# Twintig-FFC-Metacarpal-RA.net
KiCad netlist of a schematic drawn in Altium Designer
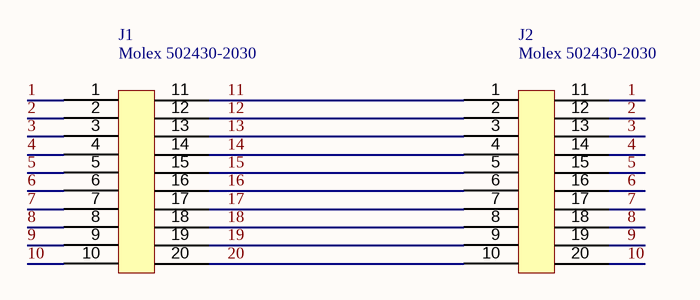
[diagram p0: Twintig-FFC-Metacarpal-RA.SchDoc]

(export (version "E")
  (design (tool "Eeschema 10.0.6"))
  (components
    (comp (ref "J1")
      (value "Molex 502430-2030")
      (footprint "Molex 502430-2030")
      (libsource (lib "x-io") (part "Molex 502430-2030"))
    )
    (comp (ref "J2")
      (value "Molex 502430-2030")
      (footprint "Molex 502430-2030")
      (libsource (lib "x-io") (part "Molex 502430-2030"))
    )
  )
  (nets
    (net (code "1") (name "/1") (class "Default")
      (node (ref "J1") (pin "1") (pinfunction "1_1") (pintype "passive"))
      (node (ref "J2") (pin "11") (pinfunction "11_11") (pintype "passive"))
    )
    (net (code "2") (name "/2") (class "Default")
      (node (ref "J1") (pin "2") (pinfunction "2_2") (pintype "passive"))
      (node (ref "J2") (pin "12") (pinfunction "12_12") (pintype "passive"))
    )
    (net (code "3") (name "/3") (class "Default")
      (node (ref "J1") (pin "3") (pinfunction "3_3") (pintype "passive"))
      (node (ref "J2") (pin "13") (pinfunction "13_13") (pintype "passive"))
    )
    (net (code "4") (name "/4") (class "Default")
      (node (ref "J1") (pin "4") (pinfunction "4_4") (pintype "passive"))
      (node (ref "J2") (pin "14") (pinfunction "14_14") (pintype "passive"))
    )
    (net (code "5") (name "/5") (class "Default")
      (node (ref "J1") (pin "5") (pinfunction "5_5") (pintype "passive"))
      (node (ref "J2") (pin "15") (pinfunction "15_15") (pintype "passive"))
    )
    (net (code "6") (name "/6") (class "Default")
      (node (ref "J1") (pin "6") (pinfunction "6_6") (pintype "passive"))
      (node (ref "J2") (pin "16") (pinfunction "16_16") (pintype "passive"))
    )
    (net (code "7") (name "/7") (class "Default")
      (node (ref "J1") (pin "7") (pinfunction "7_7") (pintype "passive"))
      (node (ref "J2") (pin "17") (pinfunction "17_17") (pintype "passive"))
    )
    (net (code "8") (name "/8") (class "Default")
      (node (ref "J1") (pin "8") (pinfunction "8_8") (pintype "passive"))
      (node (ref "J2") (pin "18") (pinfunction "18_18") (pintype "passive"))
    )
    (net (code "9") (name "/9") (class "Default")
      (node (ref "J1") (pin "9") (pinfunction "9_9") (pintype "passive"))
      (node (ref "J2") (pin "19") (pinfunction "19_19") (pintype "passive"))
    )
    (net (code "10") (name "/10") (class "Default")
      (node (ref "J1") (pin "10") (pinfunction "10_10") (pintype "passive"))
      (node (ref "J2") (pin "20") (pinfunction "20_20") (pintype "passive"))
    )
    (net (code "11") (name "/11") (class "Default")
      (node (ref "J1") (pin "11") (pinfunction "11_11") (pintype "passive"))
      (node (ref "J2") (pin "1") (pinfunction "1_1") (pintype "passive"))
    )
    (net (code "12") (name "/12") (class "Default")
      (node (ref "J1") (pin "12") (pinfunction "12_12") (pintype "passive"))
      (node (ref "J2") (pin "2") (pinfunction "2_2") (pintype "passive"))
    )
    (net (code "13") (name "/13") (class "Default")
      (node (ref "J1") (pin "13") (pinfunction "13_13") (pintype "passive"))
      (node (ref "J2") (pin "3") (pinfunction "3_3") (pintype "passive"))
    )
    (net (code "14") (name "/14") (class "Default")
      (node (ref "J1") (pin "14") (pinfunction "14_14") (pintype "passive"))
      (node (ref "J2") (pin "4") (pinfunction "4_4") (pintype "passive"))
    )
    (net (code "15") (name "/15") (class "Default")
      (node (ref "J1") (pin "15") (pinfunction "15_15") (pintype "passive"))
      (node (ref "J2") (pin "5") (pinfunction "5_5") (pintype "passive"))
    )
    (net (code "16") (name "/16") (class "Default")
      (node (ref "J1") (pin "16") (pinfunction "16_16") (pintype "passive"))
      (node (ref "J2") (pin "6") (pinfunction "6_6") (pintype "passive"))
    )
    (net (code "17") (name "/17") (class "Default")
      (node (ref "J1") (pin "17") (pinfunction "17_17") (pintype "passive"))
      (node (ref "J2") (pin "7") (pinfunction "7_7") (pintype "passive"))
    )
    (net (code "18") (name "/18") (class "Default")
      (node (ref "J1") (pin "18") (pinfunction "18_18") (pintype "passive"))
      (node (ref "J2") (pin "8") (pinfunction "8_8") (pintype "passive"))
    )
    (net (code "19") (name "/19") (class "Default")
      (node (ref "J1") (pin "19") (pinfunction "19_19") (pintype "passive"))
      (node (ref "J2") (pin "9") (pinfunction "9_9") (pintype "passive"))
    )
    (net (code "20") (name "/20") (class "Default")
      (node (ref "J1") (pin "20") (pinfunction "20_20") (pintype "passive"))
      (node (ref "J2") (pin "10") (pinfunction "10_10") (pintype "passive"))
    )
  )
)
